# TSOC_RS485_EM_R5_0.net
KiCad netlist of a schematic drawn in EAGLE
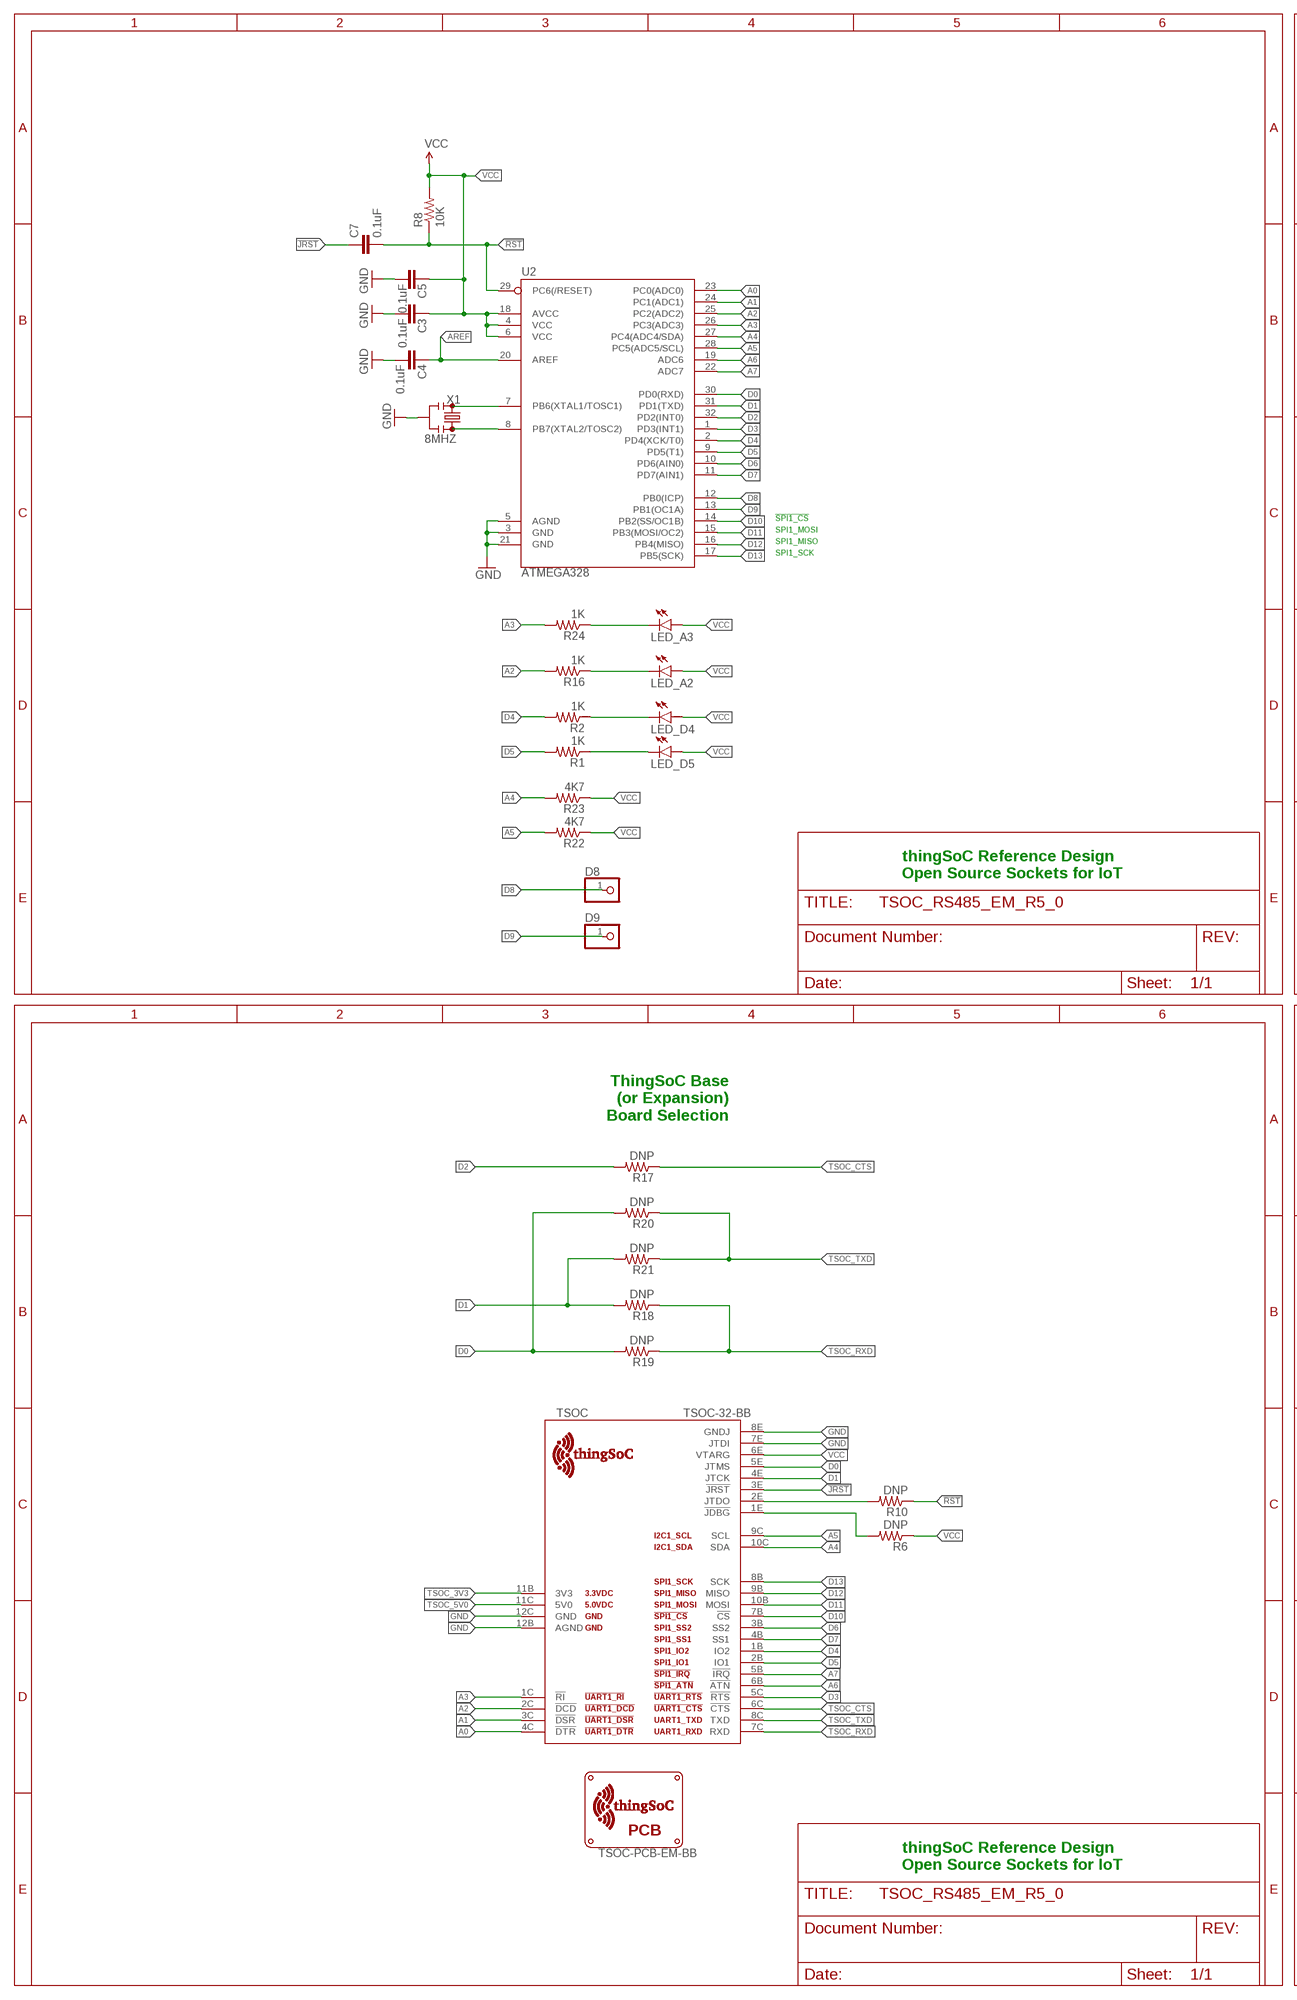
[diagram p0: schematic, sheet 1, part 1 of 2]
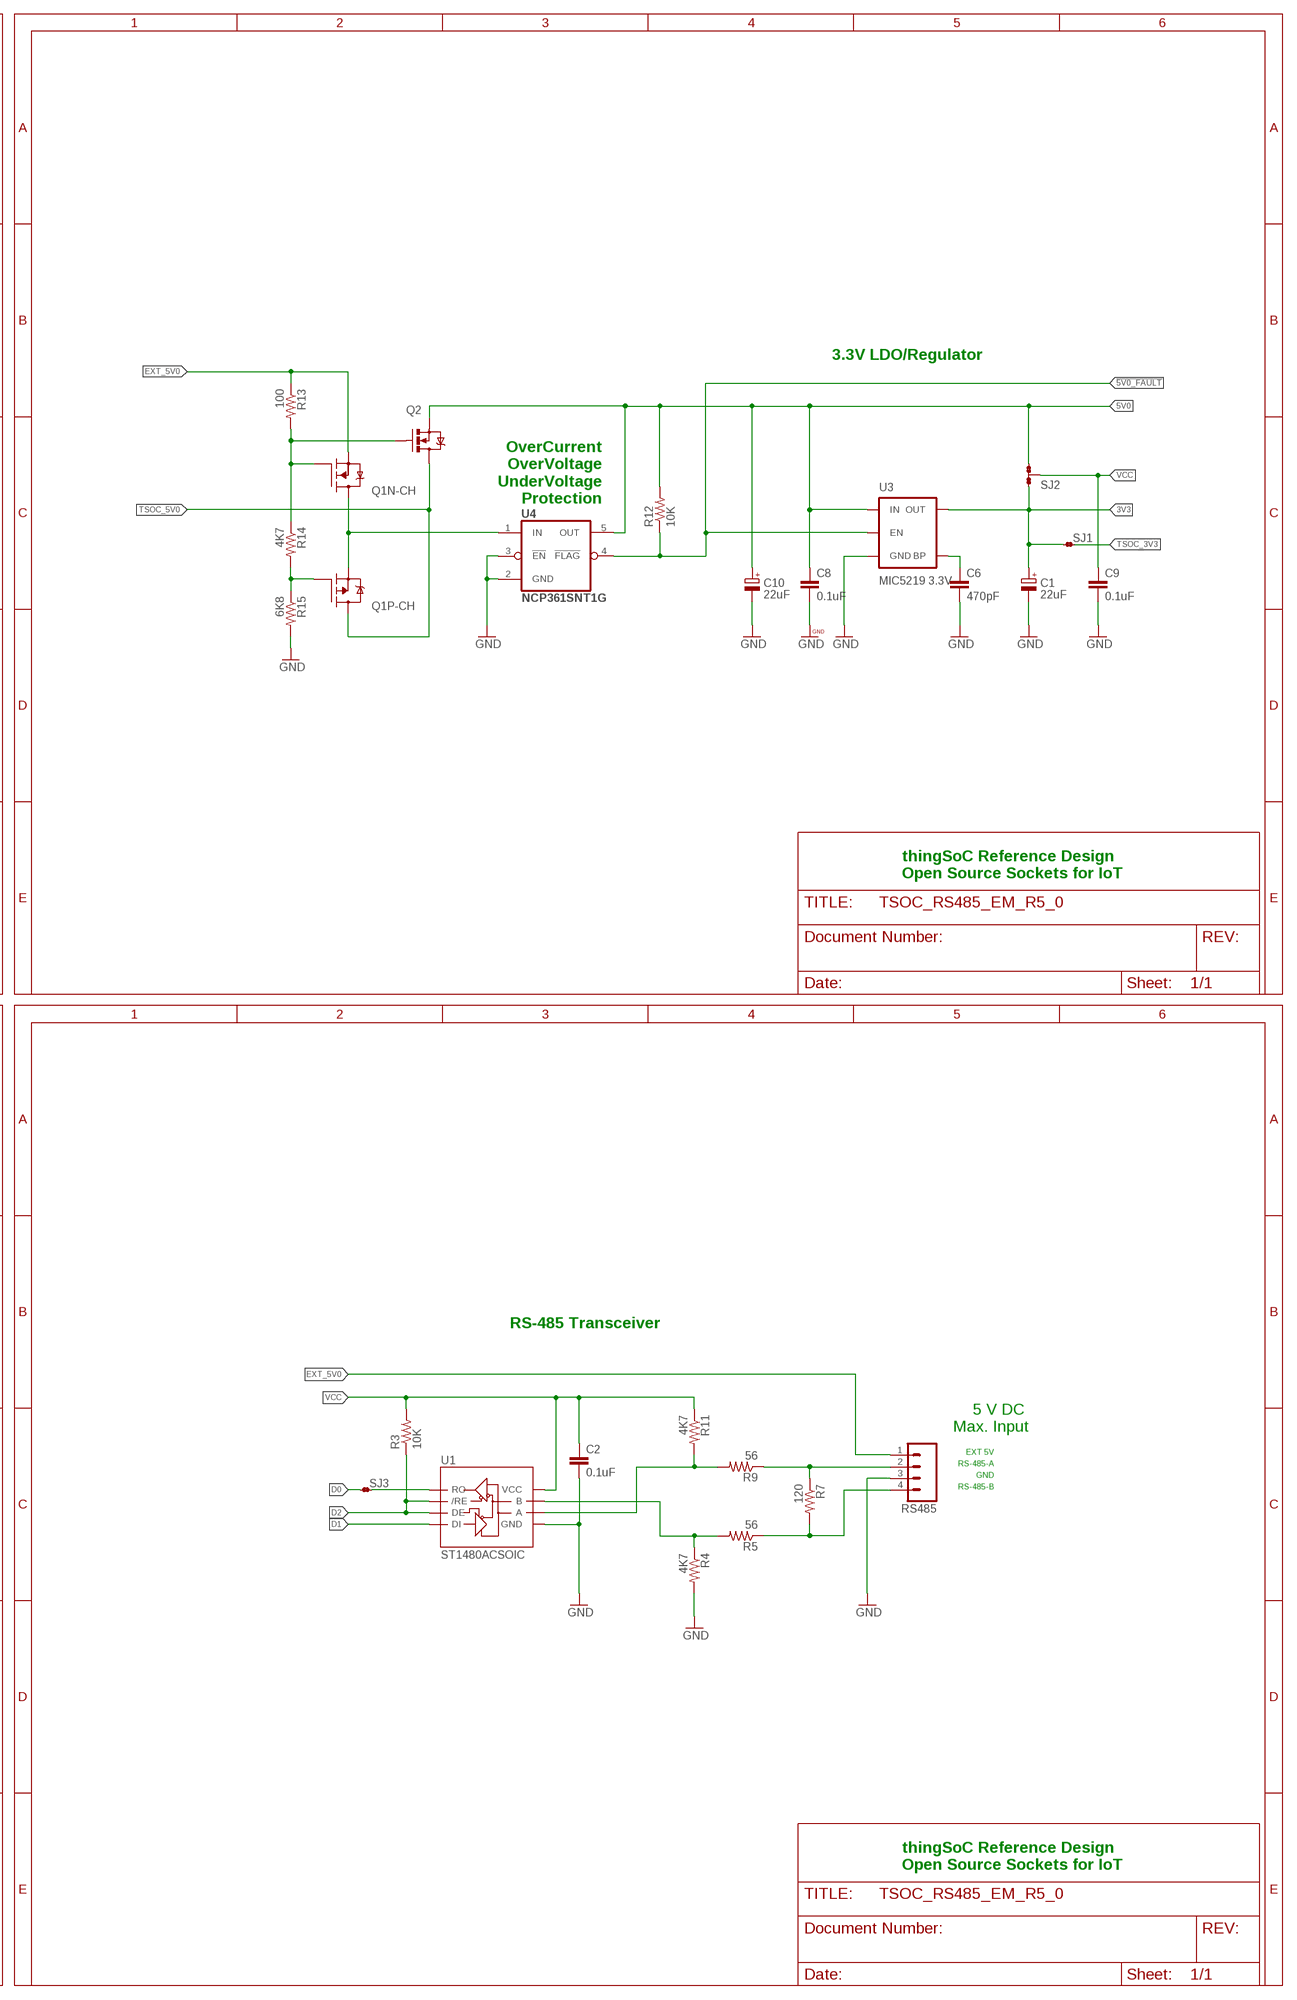
[diagram p1: schematic, sheet 1, part 2 of 2]

(export (version "E")
  (design (tool "Eeschema 10.0.6"))
  (components
    (comp (ref "C1")
      (value "22uF")
      (footprint "eagle-import:SMC_B")
      (libsource (lib "eagle-import") (part "CPOL-EUSMCB"))
    )
    (comp (ref "C2")
      (value "0.1uF")
      (footprint "eagle-import:0402-CAP")
      (libsource (lib "eagle-import") (part "CAP0402-CAP"))
    )
    (comp (ref "C3")
      (value "0.1uF")
      (footprint "eagle-import:0402-CAP")
      (libsource (lib "eagle-import") (part "CAP0402-CAP"))
    )
    (comp (ref "C4")
      (value "0.1uF")
      (footprint "eagle-import:0402-CAP")
      (libsource (lib "eagle-import") (part "CAP0402-CAP"))
    )
    (comp (ref "C5")
      (value "0.1uF")
      (footprint "eagle-import:0402-CAP")
      (libsource (lib "eagle-import") (part "CAP0402-CAP"))
    )
    (comp (ref "C6")
      (value "470pF")
      (footprint "eagle-import:0402-CAP")
      (libsource (lib "eagle-import") (part "CAP0402-CAP"))
    )
    (comp (ref "C7")
      (value "0.1uF")
      (footprint "eagle-import:0402-CAP")
      (libsource (lib "eagle-import") (part "CAP0402-CAP"))
    )
    (comp (ref "C8")
      (value "0.1uF")
      (footprint "eagle-import:0402-CAP")
      (libsource (lib "eagle-import") (part "CAP0402-CAP"))
    )
    (comp (ref "C9")
      (value "0.1uF")
      (footprint "eagle-import:0402-CAP")
      (libsource (lib "eagle-import") (part "CAP0402-CAP"))
    )
    (comp (ref "C10")
      (value "22uF")
      (footprint "eagle-import:SMC_B")
      (libsource (lib "eagle-import") (part "CPOL-EUSMCB"))
    )
    (comp (ref "D8")
      (value "WPAD-1-0402")
      (footprint "eagle-import:WPAD-1-0402")
      (libsource (lib "eagle-import") (part "WPAD-1-0402"))
    )
    (comp (ref "D9")
      (value "WPAD-1-0402")
      (footprint "eagle-import:WPAD-1-0402")
      (libsource (lib "eagle-import") (part "WPAD-1-0402"))
    )
    (comp (ref "LED_A2")
      (value "LED0603")
      (footprint "eagle-import:LED-0603")
      (libsource (lib "eagle-import") (part "LED0603"))
    )
    (comp (ref "LED_A3")
      (value "LED0603")
      (footprint "eagle-import:LED-0603")
      (libsource (lib "eagle-import") (part "LED0603"))
    )
    (comp (ref "LED_D4")
      (value "LED0603")
      (footprint "eagle-import:LED-0603")
      (libsource (lib "eagle-import") (part "LED0603"))
    )
    (comp (ref "LED_D5")
      (value "LED0603")
      (footprint "eagle-import:LED-0603")
      (libsource (lib "eagle-import") (part "LED0603"))
    )
    (comp (ref "Q1")
      (value "FDC6420C")
      (footprint "eagle-import:SOT95P280X110-6N")
      (libsource (lib "eagle-import") (part "FDC6420C"))
    )
    (comp (ref "Q2")
      (value "MOSFET-NCHANNELAO3404A")
      (footprint "eagle-import:SOT23-3")
      (libsource (lib "eagle-import") (part "MOSFET-NCHANNELAO3404A"))
    )
    (comp (ref "R1")
      (value "1K")
      (footprint "eagle-import:0402-RES")
      (libsource (lib "eagle-import") (part "RESISTOR0402"))
    )
    (comp (ref "R2")
      (value "1K")
      (footprint "eagle-import:0402-RES")
      (libsource (lib "eagle-import") (part "RESISTOR0402"))
    )
    (comp (ref "R3")
      (value "10K")
      (footprint "eagle-import:0402-RES")
      (libsource (lib "eagle-import") (part "RESISTOR0402"))
    )
    (comp (ref "R4")
      (value "4K7")
      (footprint "eagle-import:0402-RES")
      (libsource (lib "eagle-import") (part "RESISTOR0402"))
    )
    (comp (ref "R5")
      (value "56")
      (footprint "eagle-import:0402-RES")
      (libsource (lib "eagle-import") (part "RESISTOR0402"))
    )
    (comp (ref "R6")
      (value "DNP")
      (footprint "eagle-import:0402-RES")
      (libsource (lib "eagle-import") (part "RESISTOR0402"))
    )
    (comp (ref "R7")
      (value "120")
      (footprint "eagle-import:0402-RES")
      (libsource (lib "eagle-import") (part "RESISTOR0402"))
    )
    (comp (ref "R8")
      (value "10K")
      (footprint "eagle-import:0402-RES")
      (libsource (lib "eagle-import") (part "RESISTOR0402"))
    )
    (comp (ref "R9")
      (value "56")
      (footprint "eagle-import:0402-RES")
      (libsource (lib "eagle-import") (part "RESISTOR0402"))
    )
    (comp (ref "R10")
      (value "DNP")
      (footprint "eagle-import:0402-RES")
      (libsource (lib "eagle-import") (part "RESISTOR0402"))
    )
    (comp (ref "R11")
      (value "4K7")
      (footprint "eagle-import:0402-RES")
      (libsource (lib "eagle-import") (part "RESISTOR0402"))
    )
    (comp (ref "R12")
      (value "10K")
      (footprint "eagle-import:0402-RES")
      (libsource (lib "eagle-import") (part "RESISTOR0402"))
    )
    (comp (ref "R13")
      (value "100")
      (footprint "eagle-import:0402-RES")
      (libsource (lib "eagle-import") (part "RESISTOR0402"))
    )
    (comp (ref "R14")
      (value "4K7")
      (footprint "eagle-import:0402-RES")
      (libsource (lib "eagle-import") (part "RESISTOR0402"))
    )
    (comp (ref "R15")
      (value "6K8")
      (footprint "eagle-import:0402-RES")
      (libsource (lib "eagle-import") (part "RESISTOR0402"))
    )
    (comp (ref "R16")
      (value "1K")
      (footprint "eagle-import:0402-RES")
      (libsource (lib "eagle-import") (part "RESISTOR0402"))
    )
    (comp (ref "R17")
      (value "DNP")
      (footprint "eagle-import:0402-RES")
      (libsource (lib "eagle-import") (part "RESISTOR0402"))
    )
    (comp (ref "R18")
      (value "DNP")
      (footprint "eagle-import:0402-RES")
      (libsource (lib "eagle-import") (part "RESISTOR0402"))
    )
    (comp (ref "R19")
      (value "DNP")
      (footprint "eagle-import:0402-RES")
      (libsource (lib "eagle-import") (part "RESISTOR0402"))
    )
    (comp (ref "R20")
      (value "DNP")
      (footprint "eagle-import:0402-RES")
      (libsource (lib "eagle-import") (part "RESISTOR0402"))
    )
    (comp (ref "R21")
      (value "DNP")
      (footprint "eagle-import:0402-RES")
      (libsource (lib "eagle-import") (part "RESISTOR0402"))
    )
    (comp (ref "R22")
      (value "4K7")
      (footprint "eagle-import:0402-RES")
      (libsource (lib "eagle-import") (part "RESISTOR0402"))
    )
    (comp (ref "R23")
      (value "4K7")
      (footprint "eagle-import:0402-RES")
      (libsource (lib "eagle-import") (part "RESISTOR0402"))
    )
    (comp (ref "R24")
      (value "1K")
      (footprint "eagle-import:0402-RES")
      (libsource (lib "eagle-import") (part "RESISTOR0402"))
    )
    (comp (ref "RS485")
      (value "M04SCREW")
      (footprint "eagle-import:SCREWTERMINAL-3.5MM-4")
      (libsource (lib "eagle-import") (part "M04SCREW"))
    )
    (comp (ref "SJ1")
      (value "JMP-2-NC")
      (footprint "eagle-import:JMP-2-NC")
      (libsource (lib "eagle-import") (part "JMP-2-NC"))
    )
    (comp (ref "SJ2")
      (value "JMP-3-1_2")
      (footprint "eagle-import:JMP-3-1_2")
      (libsource (lib "eagle-import") (part "JMP-3-1_2"))
    )
    (comp (ref "SJ3")
      (value "JMP-2-NC")
      (footprint "eagle-import:JMP-2-NC")
      (libsource (lib "eagle-import") (part "JMP-2-NC"))
    )
    (comp (ref "TSOC")
      (value "TSOC-32-BB")
      (footprint "eagle-import:TSOC-BB-S32")
      (libsource (lib "eagle-import") (part "TSOC-32-BB"))
    )
    (comp (ref "U$1")
      (value "TSOC-PCB-EM-BB")
      (footprint "eagle-import:TSOC-EM-BB")
      (libsource (lib "eagle-import") (part "TSOC-PCB-EM-BB"))
    )
    (comp (ref "U1")
      (value "ST1480ACSOIC")
      (footprint "eagle-import:SO08")
      (libsource (lib "eagle-import") (part "ST1480ACSOIC"))
    )
    (comp (ref "U2")
      (value "ATMEGA328")
      (footprint "eagle-import:TQFP32-08")
      (libsource (lib "eagle-import") (part "ATMEGA168"))
    )
    (comp (ref "U3")
      (value "MIC5219 3.3V")
      (footprint "eagle-import:SOT23-5")
      (libsource (lib "eagle-import") (part "V_REG_MIC52193.3V"))
    )
    (comp (ref "U4")
      (value "NCP361SNT1G")
      (footprint "eagle-import:SOP95P275X110-5N")
      (libsource (lib "eagle-import") (part "NCP361SNT1G"))
    )
    (comp (ref "X1")
      (value "8MHZ")
      (footprint "eagle-import:RESONATOR-SMD")
      (libsource (lib "eagle-import") (part "RESONATOR8MHZ"))
    )
  )
  (nets
    (net (code "1") (name "/~{5V0_FAULT}") (class "Default")
      (node (ref "R12") (pin "1") (pinfunction "1_1") (pintype "passive"))
      (node (ref "U3") (pin "3") (pinfunction "EN_3") (pintype "input"))
      (node (ref "U4") (pin "4") (pinfunction "~{FLAG}_4") (pintype "input"))
    )
    (net (code "2") (name "/~{JRST}") (class "Default")
      (node (ref "C7") (pin "1") (pinfunction "1_1") (pintype "passive"))
      (node (ref "TSOC") (pin "3E") (pinfunction "~{JRST}_3E") (pintype "bidirectional"))
    )
    (net (code "3") (name "/~{RST}") (class "Default")
      (node (ref "C7") (pin "2") (pinfunction "2_2") (pintype "passive"))
      (node (ref "R10") (pin "1") (pinfunction "1_1") (pintype "passive"))
      (node (ref "R8") (pin "1") (pinfunction "1_1") (pintype "passive"))
      (node (ref "U2") (pin "29") (pinfunction "PC6(/RESET)_29") (pintype "bidirectional"))
    )
    (net (code "4") (name "3V3") (class "Default")
      (node (ref "C1") (pin "+") (pinfunction "+_+") (pintype "passive"))
      (node (ref "SJ1") (pin "1") (pinfunction "1_1") (pintype "passive"))
      (node (ref "SJ2") (pin "1") (pinfunction "1_1") (pintype "passive"))
      (node (ref "U3") (pin "5") (pinfunction "OUT_5") (pintype "passive"))
    )
    (net (code "5") (name "5V0") (class "Default")
      (node (ref "C10") (pin "+") (pinfunction "+_+") (pintype "passive"))
      (node (ref "C8") (pin "1") (pinfunction "1_1") (pintype "passive"))
      (node (ref "Q2") (pin "2") (pinfunction "S_2") (pintype "passive"))
      (node (ref "R12") (pin "2") (pinfunction "2_2") (pintype "passive"))
      (node (ref "SJ2") (pin "3") (pinfunction "3_3") (pintype "passive"))
      (node (ref "U3") (pin "1") (pinfunction "IN_1") (pintype "input"))
      (node (ref "U4") (pin "5") (pinfunction "OUT_5") (pintype "output"))
    )
    (net (code "6") (name "A0") (class "Default")
      (node (ref "TSOC") (pin "4C") (pinfunction "~{DTR}_4C") (pintype "bidirectional"))
      (node (ref "U2") (pin "23") (pinfunction "PC0(ADC0)_23") (pintype "bidirectional"))
    )
    (net (code "7") (name "A1") (class "Default")
      (node (ref "TSOC") (pin "3C") (pinfunction "~{DSR}_3C") (pintype "bidirectional"))
      (node (ref "U2") (pin "24") (pinfunction "PC1(ADC1)_24") (pintype "bidirectional"))
    )
    (net (code "8") (name "A2") (class "Default")
      (node (ref "R16") (pin "2") (pinfunction "2_2") (pintype "passive"))
      (node (ref "TSOC") (pin "2C") (pinfunction "~{DCD}_2C") (pintype "bidirectional"))
      (node (ref "U2") (pin "25") (pinfunction "PC2(ADC2)_25") (pintype "bidirectional"))
    )
    (net (code "9") (name "A3") (class "Default")
      (node (ref "R24") (pin "2") (pinfunction "2_2") (pintype "passive"))
      (node (ref "TSOC") (pin "1C") (pinfunction "~{RI}_1C") (pintype "bidirectional"))
      (node (ref "U2") (pin "26") (pinfunction "PC3(ADC3)_26") (pintype "bidirectional"))
    )
    (net (code "10") (name "A4") (class "Default")
      (node (ref "R23") (pin "2") (pinfunction "2_2") (pintype "passive"))
      (node (ref "TSOC") (pin "10C") (pinfunction "SDA_10C") (pintype "bidirectional"))
      (node (ref "U2") (pin "27") (pinfunction "PC4(ADC4/SDA)_27") (pintype "bidirectional"))
    )
    (net (code "11") (name "A5") (class "Default")
      (node (ref "R22") (pin "2") (pinfunction "2_2") (pintype "passive"))
      (node (ref "TSOC") (pin "9C") (pinfunction "SCL_9C") (pintype "bidirectional"))
      (node (ref "U2") (pin "28") (pinfunction "PC5(ADC5/SCL)_28") (pintype "bidirectional"))
    )
    (net (code "12") (name "A6") (class "Default")
      (node (ref "TSOC") (pin "6B") (pinfunction "~{ATN}_6B") (pintype "bidirectional"))
      (node (ref "U2") (pin "19") (pinfunction "ADC6_19") (pintype "bidirectional"))
    )
    (net (code "13") (name "A7") (class "Default")
      (node (ref "TSOC") (pin "5B") (pinfunction "~{IRQ}_5B") (pintype "bidirectional"))
      (node (ref "U2") (pin "22") (pinfunction "ADC7_22") (pintype "bidirectional"))
    )
    (net (code "14") (name "AREF") (class "Default")
      (node (ref "C4") (pin "2") (pinfunction "2_2") (pintype "passive"))
      (node (ref "U2") (pin "20") (pinfunction "AREF_20") (pintype "bidirectional"))
    )
    (net (code "15") (name "D0") (class "Default")
      (node (ref "R19") (pin "2") (pinfunction "2_2") (pintype "passive"))
      (node (ref "R20") (pin "2") (pinfunction "2_2") (pintype "passive"))
      (node (ref "SJ3") (pin "1") (pinfunction "1_1") (pintype "passive"))
      (node (ref "TSOC") (pin "5E") (pinfunction "JTMS_5E") (pintype "bidirectional"))
      (node (ref "U2") (pin "30") (pinfunction "PD0(RXD)_30") (pintype "bidirectional"))
    )
    (net (code "16") (name "D1") (class "Default")
      (node (ref "R18") (pin "2") (pinfunction "2_2") (pintype "passive"))
      (node (ref "R21") (pin "2") (pinfunction "2_2") (pintype "passive"))
      (node (ref "TSOC") (pin "4E") (pinfunction "JTCK_4E") (pintype "bidirectional"))
      (node (ref "U1") (pin "4") (pinfunction "DI_4") (pintype "bidirectional"))
      (node (ref "U2") (pin "31") (pinfunction "PD1(TXD)_31") (pintype "bidirectional"))
    )
    (net (code "17") (name "D2") (class "Default")
      (node (ref "R17") (pin "2") (pinfunction "2_2") (pintype "passive"))
      (node (ref "R3") (pin "1") (pinfunction "1_1") (pintype "passive"))
      (node (ref "U1") (pin "2") (pinfunction "/RE_2") (pintype "bidirectional"))
      (node (ref "U1") (pin "3") (pinfunction "DE_3") (pintype "bidirectional"))
      (node (ref "U2") (pin "32") (pinfunction "PD2(INT0)_32") (pintype "bidirectional"))
    )
    (net (code "18") (name "D3") (class "Default")
      (node (ref "TSOC") (pin "5C") (pinfunction "~{RTS}_5C") (pintype "bidirectional"))
      (node (ref "U2") (pin "1") (pinfunction "PD3(INT1)_1") (pintype "bidirectional"))
    )
    (net (code "19") (name "D4") (class "Default")
      (node (ref "R2") (pin "2") (pinfunction "2_2") (pintype "passive"))
      (node (ref "TSOC") (pin "1B") (pinfunction "IO2_1B") (pintype "bidirectional"))
      (node (ref "U2") (pin "2") (pinfunction "PD4(XCK/T0)_2") (pintype "bidirectional"))
    )
    (net (code "20") (name "D5") (class "Default")
      (node (ref "R1") (pin "2") (pinfunction "2_2") (pintype "passive"))
      (node (ref "TSOC") (pin "2B") (pinfunction "IO1_2B") (pintype "bidirectional"))
      (node (ref "U2") (pin "9") (pinfunction "PD5(T1)_9") (pintype "bidirectional"))
    )
    (net (code "21") (name "D6") (class "Default")
      (node (ref "TSOC") (pin "3B") (pinfunction "SS2_3B") (pintype "bidirectional"))
      (node (ref "U2") (pin "10") (pinfunction "PD6(AIN0)_10") (pintype "bidirectional"))
    )
    (net (code "22") (name "D7") (class "Default")
      (node (ref "TSOC") (pin "4B") (pinfunction "SS1_4B") (pintype "bidirectional"))
      (node (ref "U2") (pin "11") (pinfunction "PD7(AIN1)_11") (pintype "bidirectional"))
    )
    (net (code "23") (name "D8") (class "Default")
      (node (ref "D8") (pin "1") (pinfunction "1_1") (pintype "passive"))
      (node (ref "U2") (pin "12") (pinfunction "PB0(ICP)_12") (pintype "bidirectional"))
    )
    (net (code "24") (name "D9") (class "Default")
      (node (ref "D9") (pin "1") (pinfunction "1_1") (pintype "passive"))
      (node (ref "U2") (pin "13") (pinfunction "PB1(OC1A)_13") (pintype "bidirectional"))
    )
    (net (code "25") (name "D10") (class "Default")
      (node (ref "TSOC") (pin "7B") (pinfunction "~{CS}_7B") (pintype "bidirectional"))
      (node (ref "U2") (pin "14") (pinfunction "PB2(SS/OC1B)_14") (pintype "bidirectional"))
    )
    (net (code "26") (name "D11") (class "Default")
      (node (ref "TSOC") (pin "10B") (pinfunction "MOSI_10B") (pintype "bidirectional"))
      (node (ref "U2") (pin "15") (pinfunction "PB3(MOSI/OC2)_15") (pintype "bidirectional"))
    )
    (net (code "27") (name "D12") (class "Default")
      (node (ref "TSOC") (pin "9B") (pinfunction "MISO_9B") (pintype "bidirectional"))
      (node (ref "U2") (pin "16") (pinfunction "PB4(MISO)_16") (pintype "bidirectional"))
    )
    (net (code "28") (name "D13") (class "Default")
      (node (ref "TSOC") (pin "8B") (pinfunction "SCK_8B") (pintype "bidirectional"))
      (node (ref "U2") (pin "17") (pinfunction "PB5(SCK)_17") (pintype "bidirectional"))
    )
    (net (code "29") (name "EXT_5V0") (class "Default")
      (node (ref "Q1") (pin "5") (pinfunction "S_5") (pintype "passive"))
      (node (ref "R13") (pin "1") (pinfunction "1_1") (pintype "passive"))
      (node (ref "RS485") (pin "1") (pinfunction "1_1") (pintype "passive"))
    )
    (net (code "30") (name "GND") (class "Default")
      (node (ref "C1") (pin "-") (pinfunction "-_-") (pintype "passive"))
      (node (ref "C10") (pin "-") (pinfunction "-_-") (pintype "passive"))
      (node (ref "C2") (pin "2") (pinfunction "2_2") (pintype "passive"))
      (node (ref "C3") (pin "1") (pinfunction "1_1") (pintype "passive"))
      (node (ref "C4") (pin "1") (pinfunction "1_1") (pintype "passive"))
      (node (ref "C5") (pin "1") (pinfunction "1_1") (pintype "passive"))
      (node (ref "C6") (pin "2") (pinfunction "2_2") (pintype "passive"))
      (node (ref "C8") (pin "2") (pinfunction "2_2") (pintype "passive"))
      (node (ref "C9") (pin "2") (pinfunction "2_2") (pintype "passive"))
      (node (ref "R15") (pin "2") (pinfunction "2_2") (pintype "passive"))
      (node (ref "R4") (pin "2") (pinfunction "2_2") (pintype "passive"))
      (node (ref "RS485") (pin "3") (pinfunction "3_3") (pintype "passive"))
      (node (ref "TSOC") (pin "12B") (pinfunction "AGND_12B") (pintype "bidirectional"))
      (node (ref "TSOC") (pin "12C") (pinfunction "GND_12C") (pintype "bidirectional"))
      (node (ref "TSOC") (pin "7E") (pinfunction "JTDI_7E") (pintype "bidirectional"))
      (node (ref "TSOC") (pin "8E") (pinfunction "GNDJ_8E") (pintype "bidirectional"))
      (node (ref "U1") (pin "5") (pinfunction "GND_5") (pintype "bidirectional"))
      (node (ref "U2") (pin "21") (pinfunction "GND_21") (pintype "bidirectional"))
      (node (ref "U2") (pin "3") (pinfunction "GND_3") (pintype "bidirectional"))
      (node (ref "U2") (pin "5") (pinfunction "AGND_5") (pintype "bidirectional"))
      (node (ref "U3") (pin "2") (pinfunction "GND_2") (pintype "input"))
      (node (ref "U4") (pin "2") (pinfunction "GND_2") (pintype "passive"))
      (node (ref "U4") (pin "3") (pinfunction "~{EN}_3") (pintype "input"))
      (node (ref "X1") (pin "2") (pinfunction "2_2") (pintype "passive"))
    )
    (net (code "31") (name "Net-(LED_A2-PadC)") (class "Default")
      (node (ref "LED_A2") (pin "C") (pinfunction "C_C") (pintype "passive"))
      (node (ref "R16") (pin "1") (pinfunction "1_1") (pintype "passive"))
    )
    (net (code "32") (name "Net-(LED_A3-PadC)") (class "Default")
      (node (ref "LED_A3") (pin "C") (pinfunction "C_C") (pintype "passive"))
      (node (ref "R24") (pin "1") (pinfunction "1_1") (pintype "passive"))
    )
    (net (code "33") (name "Net-(LED_D4-PadC)") (class "Default")
      (node (ref "LED_D4") (pin "C") (pinfunction "C_C") (pintype "passive"))
      (node (ref "R2") (pin "1") (pinfunction "1_1") (pintype "passive"))
    )
    (net (code "34") (name "Net-(LED_D5-PadC)") (class "Default")
      (node (ref "LED_D5") (pin "C") (pinfunction "C_C") (pintype "passive"))
      (node (ref "R1") (pin "1") (pinfunction "1_1") (pintype "passive"))
    )
    (net (code "35") (name "Net-(Q1A-D)") (class "Default")
      (node (ref "Q1") (pin "2") (pinfunction "S_2") (pintype "passive"))
      (node (ref "Q1") (pin "6") (pinfunction "D_6") (pintype "passive"))
      (node (ref "U4") (pin "1") (pinfunction "IN_1") (pintype "power_in"))
    )
    (net (code "36") (name "Net-(Q1A-G)") (class "Default")
      (node (ref "Q1") (pin "1") (pinfunction "G_1") (pintype "passive"))
      (node (ref "Q2") (pin "1") (pinfunction "G_1") (pintype "passive"))
      (node (ref "R13") (pin "2") (pinfunction "2_2") (pintype "passive"))
      (node (ref "R14") (pin "1") (pinfunction "1_1") (pintype "passive"))
    )
    (net (code "37") (name "Net-(Q1B-G)") (class "Default")
      (node (ref "Q1") (pin "3") (pinfunction "G_3") (pintype "passive"))
      (node (ref "R14") (pin "2") (pinfunction "2_2") (pintype "passive"))
      (node (ref "R15") (pin "1") (pinfunction "1_1") (pintype "passive"))
    )
    (net (code "38") (name "Net-(R5-Pad1)") (class "Default")
      (node (ref "R5") (pin "1") (pinfunction "1_1") (pintype "passive"))
      (node (ref "R7") (pin "2") (pinfunction "2_2") (pintype "passive"))
      (node (ref "RS485") (pin "4") (pinfunction "4_4") (pintype "passive"))
    )
    (net (code "39") (name "Net-(R7-Pad1)") (class "Default")
      (node (ref "R7") (pin "1") (pinfunction "1_1") (pintype "passive"))
      (node (ref "R9") (pin "1") (pinfunction "1_1") (pintype "passive"))
      (node (ref "RS485") (pin "2") (pinfunction "2_2") (pintype "passive"))
    )
    (net (code "40") (name "Net-(TSOC-JTDO)") (class "Default")
      (node (ref "R10") (pin "2") (pinfunction "2_2") (pintype "passive"))
      (node (ref "TSOC") (pin "2E") (pinfunction "JTDO_2E") (pintype "bidirectional"))
    )
    (net (code "41") (name "Net-(TSOC-~{JDBG})") (class "Default")
      (node (ref "R6") (pin "2") (pinfunction "2_2") (pintype "passive"))
      (node (ref "TSOC") (pin "1E") (pinfunction "~{JDBG}_1E") (pintype "bidirectional"))
    )
    (net (code "42") (name "Net-(U1-A)") (class "Default")
      (node (ref "R11") (pin "2") (pinfunction "2_2") (pintype "passive"))
      (node (ref "R9") (pin "2") (pinfunction "2_2") (pintype "passive"))
      (node (ref "U1") (pin "6") (pinfunction "A_6") (pintype "bidirectional"))
    )
    (net (code "43") (name "Net-(U1-B)") (class "Default")
      (node (ref "R4") (pin "1") (pinfunction "1_1") (pintype "passive"))
      (node (ref "R5") (pin "2") (pinfunction "2_2") (pintype "passive"))
      (node (ref "U1") (pin "7") (pinfunction "B_7") (pintype "bidirectional"))
    )
    (net (code "44") (name "Net-(U1-RO)") (class "Default")
      (node (ref "SJ3") (pin "2") (pinfunction "2_2") (pintype "passive"))
      (node (ref "U1") (pin "1") (pinfunction "RO_1") (pintype "bidirectional"))
    )
    (net (code "45") (name "Net-(U2-PB6(XTAL1{slash}TOSC1))") (class "Default")
      (node (ref "U2") (pin "7") (pinfunction "PB6(XTAL1/TOSC1)_7") (pintype "bidirectional"))
      (node (ref "X1") (pin "3") (pinfunction "3_3") (pintype "passive"))
    )
    (net (code "46") (name "Net-(U2-PB7(XTAL2{slash}TOSC2))") (class "Default")
      (node (ref "U2") (pin "8") (pinfunction "PB7(XTAL2/TOSC2)_8") (pintype "bidirectional"))
      (node (ref "X1") (pin "1") (pinfunction "1_1") (pintype "passive"))
    )
    (net (code "47") (name "Net-(U3-BP)") (class "Default")
      (node (ref "C6") (pin "1") (pinfunction "1_1") (pintype "passive"))
      (node (ref "U3") (pin "4") (pinfunction "BP_4") (pintype "input"))
    )
    (net (code "48") (name "TSOC_3V3") (class "Default")
      (node (ref "SJ1") (pin "2") (pinfunction "2_2") (pintype "passive"))
      (node (ref "TSOC") (pin "11B") (pinfunction "3V3_11B") (pintype "bidirectional"))
    )
    (net (code "49") (name "TSOC_5V0") (class "Default")
      (node (ref "Q1") (pin "4") (pinfunction "D_4") (pintype "passive"))
      (node (ref "Q2") (pin "3") (pinfunction "D_3") (pintype "passive"))
      (node (ref "TSOC") (pin "11C") (pinfunction "5V0_11C") (pintype "bidirectional"))
    )
    (net (code "50") (name "TSOC_CTS") (class "Default")
      (node (ref "R17") (pin "1") (pinfunction "1_1") (pintype "passive"))
      (node (ref "TSOC") (pin "6C") (pinfunction "~{CTS}_6C") (pintype "bidirectional"))
    )
    (net (code "51") (name "TSOC_RXD") (class "Default")
      (node (ref "R18") (pin "1") (pinfunction "1_1") (pintype "passive"))
      (node (ref "R19") (pin "1") (pinfunction "1_1") (pintype "passive"))
      (node (ref "TSOC") (pin "7C") (pinfunction "RXD_7C") (pintype "bidirectional"))
    )
    (net (code "52") (name "TSOC_TXD") (class "Default")
      (node (ref "R20") (pin "1") (pinfunction "1_1") (pintype "passive"))
      (node (ref "R21") (pin "1") (pinfunction "1_1") (pintype "passive"))
      (node (ref "TSOC") (pin "8C") (pinfunction "TXD_8C") (pintype "bidirectional"))
    )
    (net (code "53") (name "VCC") (class "Default")
      (node (ref "C2") (pin "1") (pinfunction "1_1") (pintype "passive"))
      (node (ref "C3") (pin "2") (pinfunction "2_2") (pintype "passive"))
      (node (ref "C5") (pin "2") (pinfunction "2_2") (pintype "passive"))
      (node (ref "C9") (pin "1") (pinfunction "1_1") (pintype "passive"))
      (node (ref "LED_A2") (pin "A") (pinfunction "A_A") (pintype "passive"))
      (node (ref "LED_A3") (pin "A") (pinfunction "A_A") (pintype "passive"))
      (node (ref "LED_D4") (pin "A") (pinfunction "A_A") (pintype "passive"))
      (node (ref "LED_D5") (pin "A") (pinfunction "A_A") (pintype "passive"))
      (node (ref "R11") (pin "1") (pinfunction "1_1") (pintype "passive"))
      (node (ref "R22") (pin "1") (pinfunction "1_1") (pintype "passive"))
      (node (ref "R23") (pin "1") (pinfunction "1_1") (pintype "passive"))
      (node (ref "R3") (pin "2") (pinfunction "2_2") (pintype "passive"))
      (node (ref "R6") (pin "1") (pinfunction "1_1") (pintype "passive"))
      (node (ref "R8") (pin "2") (pinfunction "2_2") (pintype "passive"))
      (node (ref "SJ2") (pin "2") (pinfunction "2_2") (pintype "passive"))
      (node (ref "TSOC") (pin "6E") (pinfunction "VTARG_6E") (pintype "bidirectional"))
      (node (ref "U1") (pin "8") (pinfunction "VCC_8") (pintype "bidirectional"))
      (node (ref "U2") (pin "18") (pinfunction "AVCC_18") (pintype "bidirectional"))
      (node (ref "U2") (pin "4") (pinfunction "VCC_4") (pintype "bidirectional"))
      (node (ref "U2") (pin "6") (pinfunction "VCC_6") (pintype "bidirectional"))
    )
  )
)
